# main.net
KiCad netlist of a schematic drawn in EAGLE
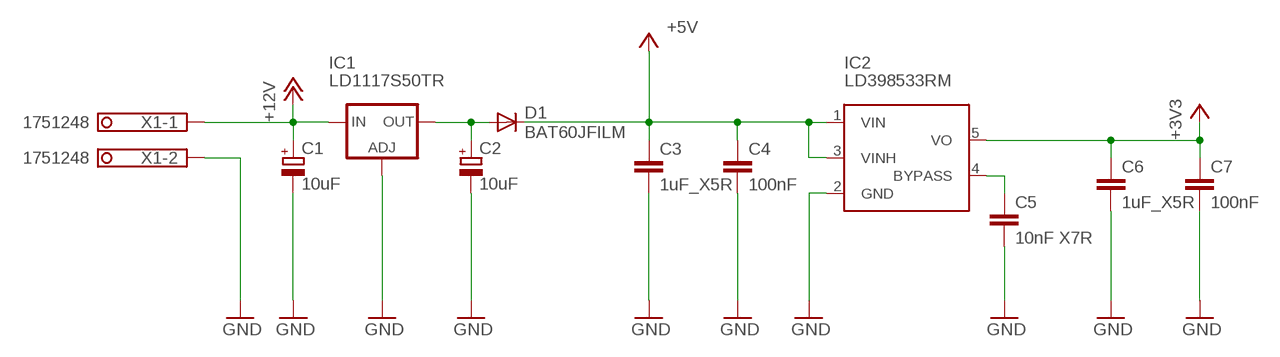
[diagram p0: schematic, sheet 1]
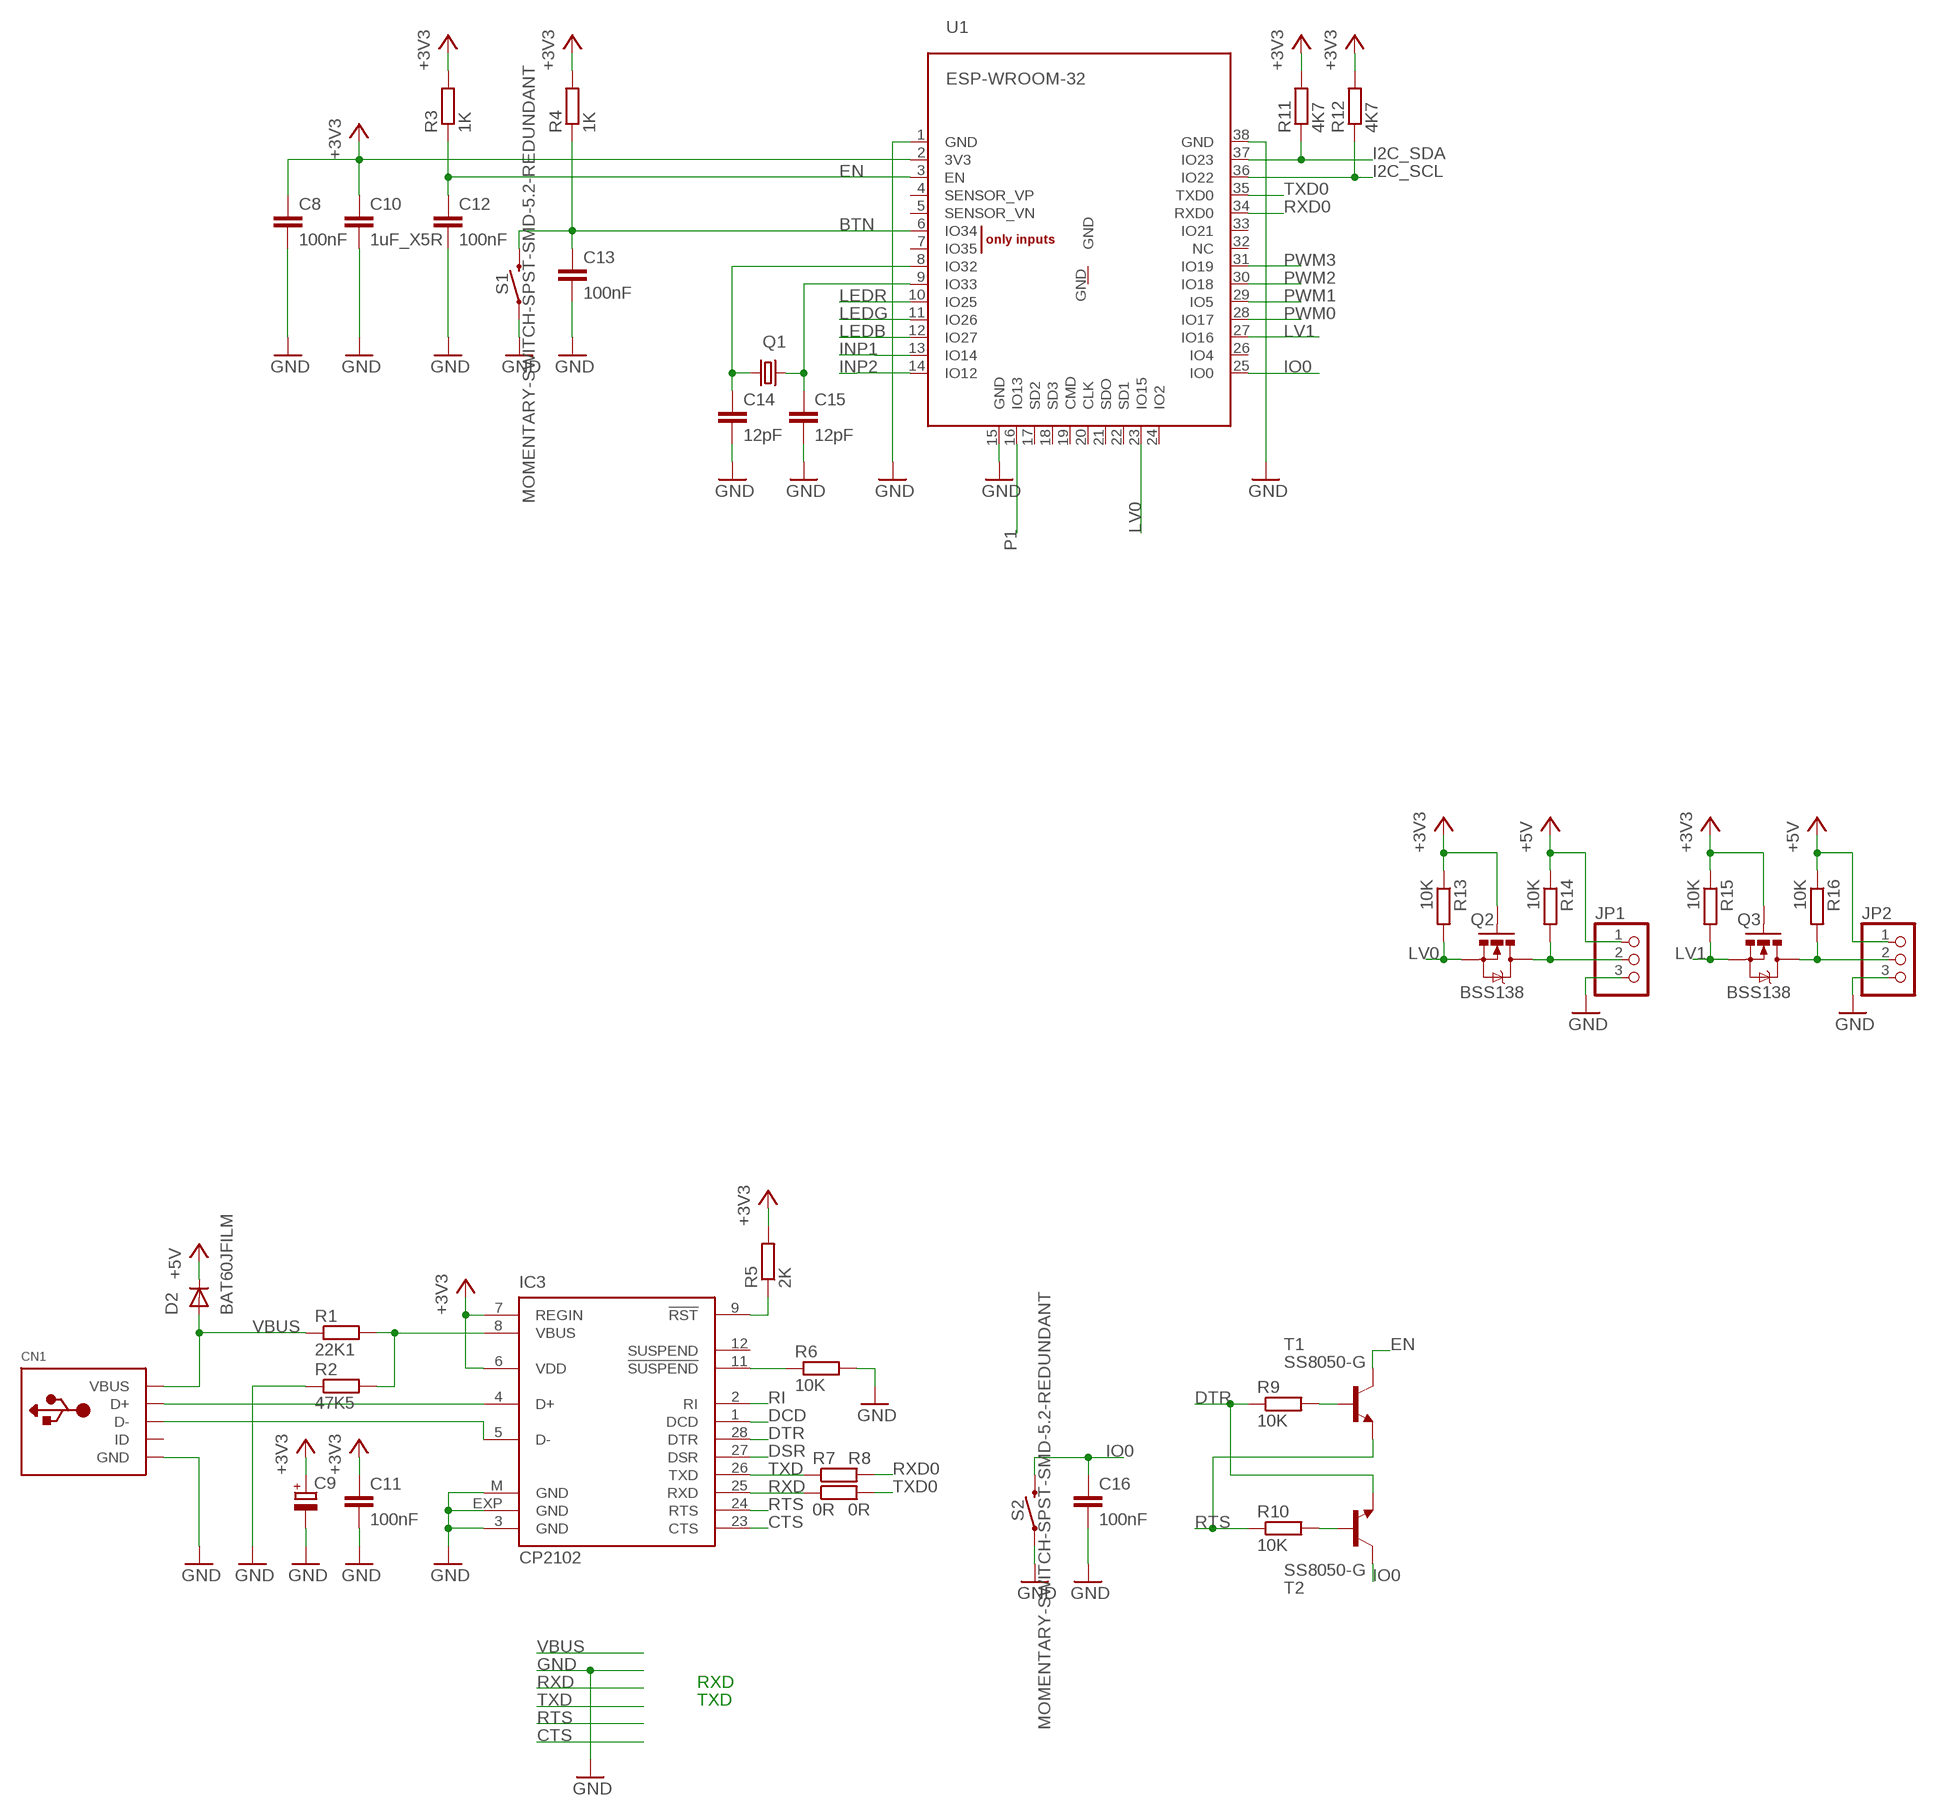
[diagram p1: schematic, sheet 2]
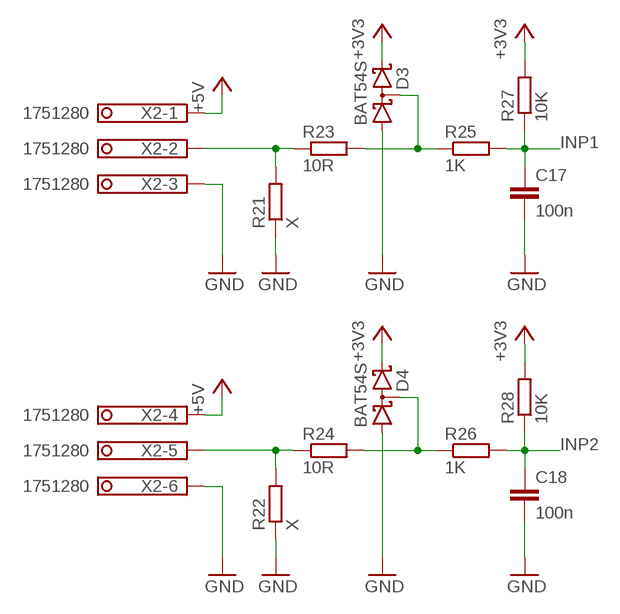
[diagram p2: schematic, sheet 3]
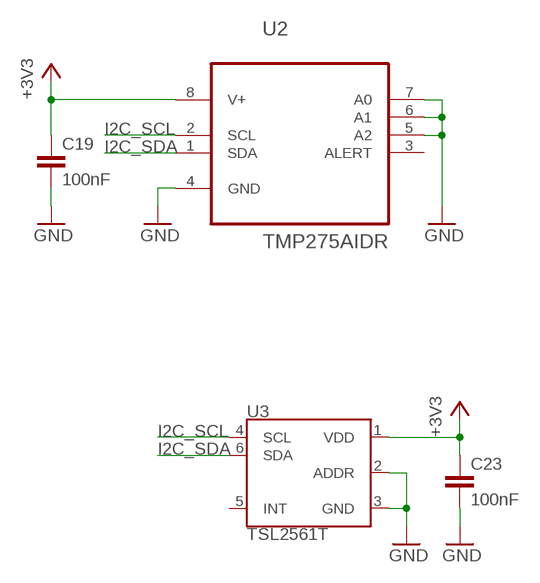
[diagram p3: schematic, sheet 4]
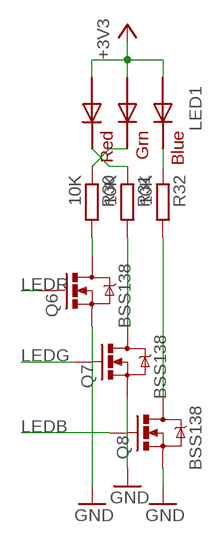
[diagram p4: schematic, sheet 5]
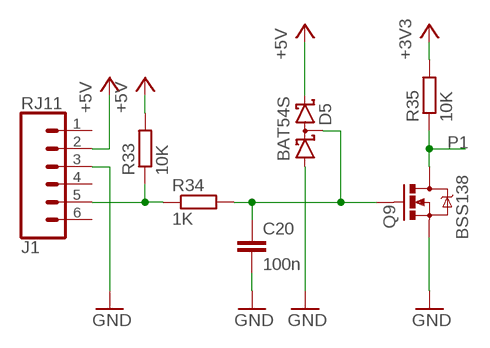
[diagram p5: schematic, sheet 6]
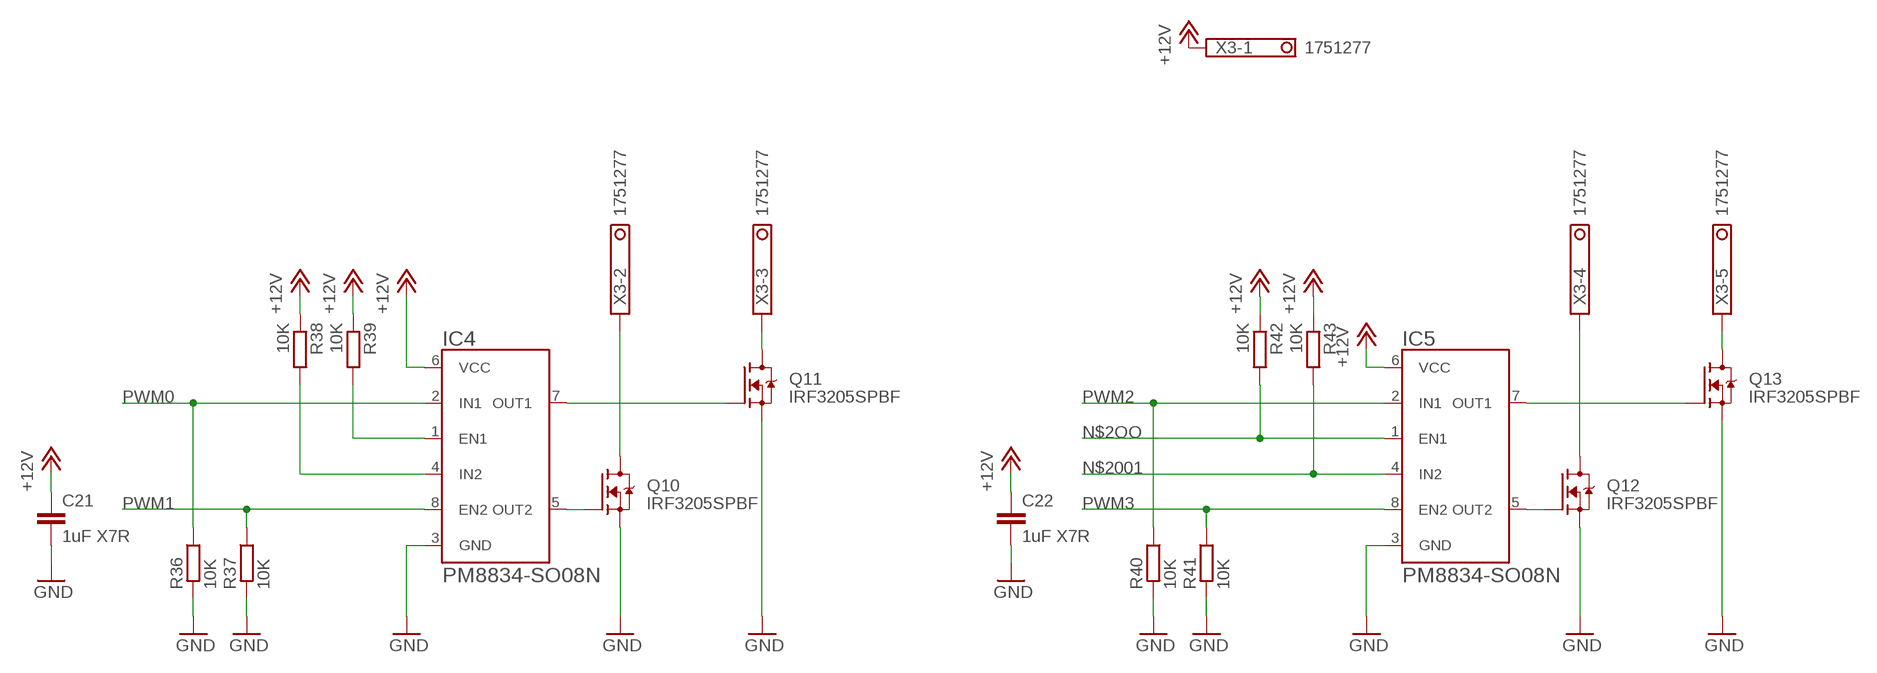
[diagram p6: schematic, sheet 7]
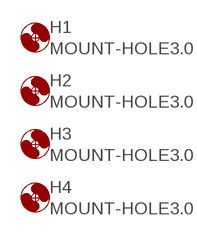
[diagram p7: schematic, sheet 8]

(export (version "E")
  (design (tool "Eeschema 10.0.6"))
  (components
    (comp (ref "C21")
      (value "1uF X7R")
      (footprint "eagle-import:C0805")
      (libsource (lib "eagle-import") (part "resistor_348_C-EUC0805"))
    )
    (comp (ref "C22")
      (value "1uF X7R")
      (footprint "eagle-import:C0805")
      (libsource (lib "eagle-import") (part "resistor_348_C-EUC0805"))
    )
    (comp (ref "IC4")
      (value "PM8834-SO08N")
      (footprint "eagle-import:SO08N")
      (fields (field (name "MF") "STMicroelectronics") (field (name "MP") "PM8834"))
      (libsource (lib "eagle-import") (part "PM8834-SO08N"))
    )
    (comp (ref "IC5")
      (value "PM8834-SO08N")
      (footprint "eagle-import:SO08N")
      (fields (field (name "MF") "STMicroelectronics") (field (name "MP") "PM8834"))
      (libsource (lib "eagle-import") (part "PM8834-SO08N"))
    )
    (comp (ref "Q10")
      (value "IRF3205SPBF")
      (footprint "eagle-import:TRANS_IRF3205SPBF")
      (fields (field (name "MF") "Infineon Technologies"))
      (libsource (lib "eagle-import") (part "IRF3205SPBF"))
    )
    (comp (ref "Q11")
      (value "IRF3205SPBF")
      (footprint "eagle-import:TRANS_IRF3205SPBF")
      (fields (field (name "MF") "Infineon Technologies"))
      (libsource (lib "eagle-import") (part "IRF3205SPBF"))
    )
    (comp (ref "Q12")
      (value "IRF3205SPBF")
      (footprint "eagle-import:TRANS_IRF3205SPBF")
      (fields (field (name "MF") "Infineon Technologies"))
      (libsource (lib "eagle-import") (part "IRF3205SPBF"))
    )
    (comp (ref "Q13")
      (value "IRF3205SPBF")
      (footprint "eagle-import:TRANS_IRF3205SPBF")
      (fields (field (name "MF") "Infineon Technologies"))
      (libsource (lib "eagle-import") (part "IRF3205SPBF"))
    )
    (comp (ref "R36")
      (value "10K")
      (footprint "eagle-import:R0805")
      (libsource (lib "eagle-import") (part "resistor_348_R-EU_R0805"))
    )
    (comp (ref "R37")
      (value "10K")
      (footprint "eagle-import:R0805")
      (libsource (lib "eagle-import") (part "resistor_348_R-EU_R0805"))
    )
    (comp (ref "R38")
      (value "10K")
      (footprint "eagle-import:R0805")
      (libsource (lib "eagle-import") (part "resistor_348_R-EU_R0805"))
    )
    (comp (ref "R39")
      (value "10K")
      (footprint "eagle-import:R0805")
      (libsource (lib "eagle-import") (part "resistor_348_R-EU_R0805"))
    )
    (comp (ref "R40")
      (value "10K")
      (footprint "eagle-import:R0805")
      (libsource (lib "eagle-import") (part "resistor_348_R-EU_R0805"))
    )
    (comp (ref "R41")
      (value "10K")
      (footprint "eagle-import:R0805")
      (libsource (lib "eagle-import") (part "resistor_348_R-EU_R0805"))
    )
    (comp (ref "R42")
      (value "10K")
      (footprint "eagle-import:R0805")
      (libsource (lib "eagle-import") (part "resistor_348_R-EU_R0805"))
    )
    (comp (ref "R43")
      (value "10K")
      (footprint "eagle-import:R0805")
      (libsource (lib "eagle-import") (part "resistor_348_R-EU_R0805"))
    )
    (comp (ref "X3")
      (value "1751277")
      (footprint "eagle-import:1751277")
      (libsource (lib "eagle-import") (part "1751277"))
    )
    (comp (ref "C20")
      (value "100n")
      (footprint "eagle-import:C0805")
      (libsource (lib "eagle-import") (part "resistor_348_C-EUC0805"))
    )
    (comp (ref "D5")
      (value "BAT54S")
      (footprint "eagle-import:SOT23")
      (libsource (lib "eagle-import") (part "BAT54S"))
    )
    (comp (ref "J1")
      (value "RJ11")
      (footprint "eagle-import:RJ11-6")
      (libsource (lib "eagle-import") (part "RJ11-6"))
    )
    (comp (ref "Q9")
      (value "BSS138")
      (footprint "eagle-import:SOT23-3")
      (libsource (lib "eagle-import") (part "MOSFET-NCHANNELSMD"))
    )
    (comp (ref "R33")
      (value "10K")
      (footprint "eagle-import:R0805")
      (libsource (lib "eagle-import") (part "resistor_348_R-EU_R0805"))
    )
    (comp (ref "R34")
      (value "1K")
      (footprint "eagle-import:R0805")
      (libsource (lib "eagle-import") (part "resistor_348_R-EU_R0805"))
    )
    (comp (ref "R35")
      (value "10K")
      (footprint "eagle-import:R0805")
      (libsource (lib "eagle-import") (part "resistor_348_R-EU_R0805"))
    )
    (comp (ref "C8")
      (value "100nF")
      (footprint "eagle-import:C0805")
      (libsource (lib "eagle-import") (part "resistor_348_C-EUC0805"))
    )
    (comp (ref "C9")
      (value "CPOL-EUSMCA")
      (footprint "eagle-import:SMC_A")
      (libsource (lib "eagle-import") (part "CPOL-EUSMCA"))
    )
    (comp (ref "C10")
      (value "1uF_X5R")
      (footprint "eagle-import:C0805")
      (libsource (lib "eagle-import") (part "resistor_348_C-EUC0805"))
    )
    (comp (ref "C11")
      (value "100nF")
      (footprint "eagle-import:C0805")
      (libsource (lib "eagle-import") (part "resistor_348_C-EUC0805"))
    )
    (comp (ref "C12")
      (value "100nF")
      (footprint "eagle-import:C0805")
      (libsource (lib "eagle-import") (part "resistor_348_C-EUC0805"))
    )
    (comp (ref "C13")
      (value "100nF")
      (footprint "eagle-import:C0805")
      (libsource (lib "eagle-import") (part "resistor_348_C-EUC0805"))
    )
    (comp (ref "C14")
      (value "12pF")
      (footprint "eagle-import:C0805")
      (libsource (lib "eagle-import") (part "resistor_348_C-EUC0805"))
    )
    (comp (ref "C15")
      (value "12pF")
      (footprint "eagle-import:C0805")
      (libsource (lib "eagle-import") (part "resistor_348_C-EUC0805"))
    )
    (comp (ref "C16")
      (value "100nF")
      (footprint "eagle-import:C0805")
      (libsource (lib "eagle-import") (part "resistor_348_C-EUC0805"))
    )
    (comp (ref "CN1")
      (value "USBMINIB")
      (footprint "eagle-import:USB-MINIB")
      (libsource (lib "eagle-import") (part "USBMINIB"))
    )
    (comp (ref "D2")
      (value "BAT60JFILM")
      (footprint "eagle-import:SOD323-W")
      (libsource (lib "eagle-import") (part "DIODE-SOD323-W"))
    )
    (comp (ref "IC3")
      (value "CP2102")
      (footprint "eagle-import:MLP28")
      (fields (field (name "MF") "FARNELL") (field (name "MPN") "CP2102-GM"))
      (libsource (lib "eagle-import") (part "CP2102"))
    )
    (comp (ref "JP1")
      (value "PINHD-1X3")
      (footprint "eagle-import:1X03")
      (libsource (lib "eagle-import") (part "PINHD-1X3"))
    )
    (comp (ref "JP2")
      (value "PINHD-1X3")
      (footprint "eagle-import:1X03")
      (libsource (lib "eagle-import") (part "PINHD-1X3"))
    )
    (comp (ref "Q1")
      (value "CRYSTALTC38H")
      (footprint "eagle-import:TC38H")
      (libsource (lib "eagle-import") (part "CRYSTALTC38H"))
    )
    (comp (ref "Q2")
      (value "BSS138")
      (footprint "eagle-import:SOT23-3")
      (libsource (lib "eagle-import") (part "MOSFET-NCHANNELSMD"))
    )
    (comp (ref "Q3")
      (value "BSS138")
      (footprint "eagle-import:SOT23-3")
      (libsource (lib "eagle-import") (part "MOSFET-NCHANNELSMD"))
    )
    (comp (ref "R1")
      (value "22K1")
      (footprint "eagle-import:R0805")
      (libsource (lib "eagle-import") (part "resistor_348_R-EU_R0805"))
    )
    (comp (ref "R2")
      (value "47K5")
      (footprint "eagle-import:R0805")
      (libsource (lib "eagle-import") (part "resistor_348_R-EU_R0805"))
    )
    (comp (ref "R3")
      (value "1K")
      (footprint "eagle-import:R0805")
      (libsource (lib "eagle-import") (part "R-EU_R0805"))
    )
    (comp (ref "R4")
      (value "1K")
      (footprint "eagle-import:R0805")
      (libsource (lib "eagle-import") (part "R-EU_R0805"))
    )
    (comp (ref "R5")
      (value "2K")
      (footprint "eagle-import:R0805")
      (libsource (lib "eagle-import") (part "resistor_348_R-EU_R0805"))
    )
    (comp (ref "R6")
      (value "10K")
      (footprint "eagle-import:R0805")
      (libsource (lib "eagle-import") (part "resistor_348_R-EU_R0805"))
    )
    (comp (ref "R7")
      (value "0R")
      (footprint "eagle-import:R0805")
      (libsource (lib "eagle-import") (part "resistor_348_R-EU_R0805"))
    )
    (comp (ref "R8")
      (value "0R")
      (footprint "eagle-import:R0805")
      (libsource (lib "eagle-import") (part "resistor_348_R-EU_R0805"))
    )
    (comp (ref "R9")
      (value "10K")
      (footprint "eagle-import:R0805")
      (libsource (lib "eagle-import") (part "R-EU_R0805"))
    )
    (comp (ref "R10")
      (value "10K")
      (footprint "eagle-import:R0805")
      (libsource (lib "eagle-import") (part "R-EU_R0805"))
    )
    (comp (ref "R11")
      (value "4K7")
      (footprint "eagle-import:R0805")
      (libsource (lib "eagle-import") (part "resistor_348_R-EU_R0805"))
    )
    (comp (ref "R12")
      (value "4K7")
      (footprint "eagle-import:R0805")
      (libsource (lib "eagle-import") (part "resistor_348_R-EU_R0805"))
    )
    (comp (ref "R13")
      (value "10K")
      (footprint "eagle-import:R0805")
      (libsource (lib "eagle-import") (part "resistor_348_R-EU_R0805"))
    )
    (comp (ref "R14")
      (value "10K")
      (footprint "eagle-import:R0805")
      (libsource (lib "eagle-import") (part "resistor_348_R-EU_R0805"))
    )
    (comp (ref "R15")
      (value "10K")
      (footprint "eagle-import:R0805")
      (libsource (lib "eagle-import") (part "resistor_348_R-EU_R0805"))
    )
    (comp (ref "R16")
      (value "10K")
      (footprint "eagle-import:R0805")
      (libsource (lib "eagle-import") (part "resistor_348_R-EU_R0805"))
    )
    (comp (ref "S1")
      (value "MOMENTARY-SWITCH-SPST-SMD-5.2-REDUNDANT")
      (footprint "eagle-import:TACTILE_SWITCH_SMD_5.2MM")
      (libsource (lib "eagle-import") (part "MOMENTARY-SWITCH-SPST-SMD-5.2-REDUNDANT"))
    )
    (comp (ref "S2")
      (value "MOMENTARY-SWITCH-SPST-SMD-5.2-REDUNDANT")
      (footprint "eagle-import:TACTILE_SWITCH_SMD_5.2MM")
      (libsource (lib "eagle-import") (part "MOMENTARY-SWITCH-SPST-SMD-5.2-REDUNDANT"))
    )
    (comp (ref "T1")
      (value "SS8050-G")
      (footprint "eagle-import:SOT23-BEC")
      (libsource (lib "eagle-import") (part "-NPN-SOT23-BECBCF29"))
    )
    (comp (ref "T2")
      (value "SS8050-G")
      (footprint "eagle-import:SOT23-BEC")
      (libsource (lib "eagle-import") (part "-NPN-SOT23-BECBCF29"))
    )
    (comp (ref "U1")
      (value "ESP-WROOM-32")
      (footprint "eagle-import:ESP-WROOM-32")
      (libsource (lib "eagle-import") (part "ESP-WROOM-32"))
    )
    (comp (ref "C19")
      (value "100nF")
      (footprint "eagle-import:C0805")
      (libsource (lib "eagle-import") (part "C-EUC0805"))
    )
    (comp (ref "C23")
      (value "100nF")
      (footprint "eagle-import:C0805")
      (libsource (lib "eagle-import") (part "C-EUC0805"))
    )
    (comp (ref "U2")
      (value "TMP275AIDR")
      (footprint "eagle-import:SOIC127P600X175-8N")
      (fields (field (name "MF") "Texas Instruments"))
      (libsource (lib "eagle-import") (part "TMP275AIDR"))
    )
    (comp (ref "U3")
      (value "TSL2561T")
      (footprint "eagle-import:TMB-6")
      (libsource (lib "eagle-import") (part "TSL2561T"))
    )
    (comp (ref "C1")
      (value "10uF")
      (footprint "eagle-import:SMC_C")
      (libsource (lib "eagle-import") (part "CPOL-EUSMCC"))
    )
    (comp (ref "C2")
      (value "10uF")
      (footprint "eagle-import:SMC_C")
      (libsource (lib "eagle-import") (part "CPOL-EUSMCC"))
    )
    (comp (ref "C3")
      (value "1uF_X5R")
      (footprint "eagle-import:C0805")
      (libsource (lib "eagle-import") (part "resistor_348_C-EUC0805"))
    )
    (comp (ref "C4")
      (value "100nF")
      (footprint "eagle-import:C0805")
      (libsource (lib "eagle-import") (part "resistor_348_C-EUC0805"))
    )
    (comp (ref "C5")
      (value "10nF X7R")
      (footprint "eagle-import:C0805")
      (libsource (lib "eagle-import") (part "resistor_348_C-EUC0805"))
    )
    (comp (ref "C6")
      (value "1uF_X5R")
      (footprint "eagle-import:C0805")
      (libsource (lib "eagle-import") (part "resistor_348_C-EUC0805"))
    )
    (comp (ref "C7")
      (value "100nF")
      (footprint "eagle-import:C0805")
      (libsource (lib "eagle-import") (part "resistor_348_C-EUC0805"))
    )
    (comp (ref "D1")
      (value "BAT60JFILM")
      (footprint "eagle-import:SOD323-W")
      (libsource (lib "eagle-import") (part "DIODE-SOD323-W"))
    )
    (comp (ref "IC1")
      (value "LD1117S50TR")
      (footprint "eagle-import:SOT223")
      (libsource (lib "eagle-import") (part "LD117A?S50TR"))
    )
    (comp (ref "IC2")
      (value "LD398533RM")
      (footprint "eagle-import:SOT23-5L")
      (libsource (lib "eagle-import") (part "LD3985M33R"))
    )
    (comp (ref "X1")
      (value "1751248")
      (footprint "eagle-import:1751248")
      (libsource (lib "eagle-import") (part "1751248"))
    )
    (comp (ref "C17")
      (value "100n")
      (footprint "eagle-import:C0805")
      (libsource (lib "eagle-import") (part "resistor_348_C-EUC0805"))
    )
    (comp (ref "C18")
      (value "100n")
      (footprint "eagle-import:C0805")
      (libsource (lib "eagle-import") (part "resistor_348_C-EUC0805"))
    )
    (comp (ref "D3")
      (value "BAT54S")
      (footprint "eagle-import:SOT23")
      (libsource (lib "eagle-import") (part "BAT54S"))
    )
    (comp (ref "D4")
      (value "BAT54S")
      (footprint "eagle-import:SOT23")
      (libsource (lib "eagle-import") (part "BAT54S"))
    )
    (comp (ref "R21")
      (value "X")
      (footprint "eagle-import:R0805")
      (libsource (lib "eagle-import") (part "resistor_348_R-EU_R0805"))
    )
    (comp (ref "R22")
      (value "X")
      (footprint "eagle-import:R0805")
      (libsource (lib "eagle-import") (part "resistor_348_R-EU_R0805"))
    )
    (comp (ref "R23")
      (value "10R")
      (footprint "eagle-import:R0805")
      (libsource (lib "eagle-import") (part "resistor_348_R-EU_R0805"))
    )
    (comp (ref "R24")
      (value "10R")
      (footprint "eagle-import:R0805")
      (libsource (lib "eagle-import") (part "resistor_348_R-EU_R0805"))
    )
    (comp (ref "R25")
      (value "1K")
      (footprint "eagle-import:R0805")
      (libsource (lib "eagle-import") (part "resistor_348_R-EU_R0805"))
    )
    (comp (ref "R26")
      (value "1K")
      (footprint "eagle-import:R0805")
      (libsource (lib "eagle-import") (part "resistor_348_R-EU_R0805"))
    )
    (comp (ref "R27")
      (value "10K")
      (footprint "eagle-import:R0805")
      (libsource (lib "eagle-import") (part "resistor_348_R-EU_R0805"))
    )
    (comp (ref "R28")
      (value "10K")
      (footprint "eagle-import:R0805")
      (libsource (lib "eagle-import") (part "resistor_348_R-EU_R0805"))
    )
    (comp (ref "X2")
      (value "1751280")
      (footprint "eagle-import:1751280")
      (libsource (lib "eagle-import") (part "1751280"))
    )
    (comp (ref "H1")
      (value "MOUNT-HOLE3.0")
      (footprint "eagle-import:3,0")
      (libsource (lib "eagle-import") (part "MOUNT-HOLE3.0"))
    )
    (comp (ref "H2")
      (value "MOUNT-HOLE3.0")
      (footprint "eagle-import:3,0")
      (libsource (lib "eagle-import") (part "MOUNT-HOLE3.0"))
    )
    (comp (ref "H3")
      (value "MOUNT-HOLE3.0")
      (footprint "eagle-import:3,0")
      (libsource (lib "eagle-import") (part "MOUNT-HOLE3.0"))
    )
    (comp (ref "H4")
      (value "MOUNT-HOLE3.0")
      (footprint "eagle-import:3,0")
      (libsource (lib "eagle-import") (part "MOUNT-HOLE3.0"))
    )
    (comp (ref "LED1")
      (value "RGBLED5050")
      (footprint "eagle-import:RGBLED5050")
      (libsource (lib "eagle-import") (part "RGBLED5050"))
    )
    (comp (ref "Q6")
      (value "BSS138")
      (footprint "eagle-import:SOT23-3")
      (libsource (lib "eagle-import") (part "MOSFET-NCHANNELSMD"))
    )
    (comp (ref "Q7")
      (value "BSS138")
      (footprint "eagle-import:SOT23-3")
      (libsource (lib "eagle-import") (part "MOSFET-NCHANNELSMD"))
    )
    (comp (ref "Q8")
      (value "BSS138")
      (footprint "eagle-import:SOT23-3")
      (libsource (lib "eagle-import") (part "MOSFET-NCHANNELSMD"))
    )
    (comp (ref "R30")
      (value "10K")
      (footprint "eagle-import:R0805")
      (libsource (lib "eagle-import") (part "resistor_348_R-EU_R0805"))
    )
    (comp (ref "R31")
      (value "10K")
      (footprint "eagle-import:R0805")
      (libsource (lib "eagle-import") (part "resistor_348_R-EU_R0805"))
    )
    (comp (ref "R32")
      (value "10K")
      (footprint "eagle-import:R0805")
      (libsource (lib "eagle-import") (part "resistor_348_R-EU_R0805"))
    )
  )
  (nets
    (net (code "1") (name "+3V3") (class "Default")
      (node (ref "C10") (pin "1") (pinfunction "1_1") (pintype "passive"))
      (node (ref "C11") (pin "1") (pinfunction "1_1") (pintype "passive"))
      (node (ref "C19") (pin "1") (pinfunction "1_1") (pintype "passive"))
      (node (ref "C23") (pin "1") (pinfunction "1_1") (pintype "passive"))
      (node (ref "C6") (pin "1") (pinfunction "1_1") (pintype "passive"))
      (node (ref "C7") (pin "1") (pinfunction "1_1") (pintype "passive"))
      (node (ref "C8") (pin "1") (pinfunction "1_1") (pintype "passive"))
      (node (ref "C9") (pin "+") (pinfunction "+_+") (pintype "passive"))
      (node (ref "D3") (pin "2") (pinfunction "C2_2") (pintype "passive"))
      (node (ref "D4") (pin "2") (pinfunction "C2_2") (pintype "passive"))
      (node (ref "IC2") (pin "5") (pinfunction "VO_5") (pintype "output"))
      (node (ref "IC3") (pin "6") (pinfunction "VDD_6") (pintype "power_in"))
      (node (ref "IC3") (pin "7") (pinfunction "REGIN_7") (pintype "passive"))
      (node (ref "LED1") (pin "1") (pinfunction "GREEN_A_1") (pintype "bidirectional"))
      (node (ref "LED1") (pin "2") (pinfunction "RED_A_2") (pintype "bidirectional"))
      (node (ref "LED1") (pin "3") (pinfunction "BLUE_A_3") (pintype "bidirectional"))
      (node (ref "Q2") (pin "1") (pinfunction "G_1") (pintype "passive"))
      (node (ref "Q3") (pin "1") (pinfunction "G_1") (pintype "passive"))
      (node (ref "R11") (pin "2") (pinfunction "2_2") (pintype "passive"))
      (node (ref "R12") (pin "2") (pinfunction "2_2") (pintype "passive"))
      (node (ref "R13") (pin "1") (pinfunction "1_1") (pintype "passive"))
      (node (ref "R15") (pin "1") (pinfunction "1_1") (pintype "passive"))
      (node (ref "R27") (pin "2") (pinfunction "2_2") (pintype "passive"))
      (node (ref "R28") (pin "2") (pinfunction "2_2") (pintype "passive"))
      (node (ref "R3") (pin "2") (pinfunction "2_2") (pintype "passive"))
      (node (ref "R35") (pin "2") (pinfunction "2_2") (pintype "passive"))
      (node (ref "R4") (pin "2") (pinfunction "2_2") (pintype "passive"))
      (node (ref "R5") (pin "2") (pinfunction "2_2") (pintype "passive"))
      (node (ref "U1") (pin "2") (pinfunction "3V3_2") (pintype "bidirectional"))
      (node (ref "U2") (pin "8") (pinfunction "V+_8") (pintype "power_in"))
      (node (ref "U3") (pin "1") (pinfunction "VDD_1") (pintype "power_in"))
    )
    (net (code "2") (name "+5V") (class "Default")
      (node (ref "C3") (pin "1") (pinfunction "1_1") (pintype "passive"))
      (node (ref "C4") (pin "1") (pinfunction "1_1") (pintype "passive"))
      (node (ref "D1") (pin "C") (pinfunction "C_C") (pintype "passive"))
      (node (ref "D2") (pin "C") (pinfunction "C_C") (pintype "passive"))
      (node (ref "D5") (pin "2") (pinfunction "C2_2") (pintype "passive"))
      (node (ref "IC2") (pin "1") (pinfunction "VIN_1") (pintype "input"))
      (node (ref "IC2") (pin "3") (pinfunction "VINH_3") (pintype "input"))
      (node (ref "J1") (pin "2") (pinfunction "2_2") (pintype "passive"))
      (node (ref "JP1") (pin "1") (pinfunction "1_1") (pintype "passive"))
      (node (ref "JP2") (pin "1") (pinfunction "1_1") (pintype "passive"))
      (node (ref "R14") (pin "1") (pinfunction "1_1") (pintype "passive"))
      (node (ref "R16") (pin "1") (pinfunction "1_1") (pintype "passive"))
      (node (ref "R33") (pin "2") (pinfunction "2_2") (pintype "passive"))
      (node (ref "X2") (pin "1") (pinfunction "K_1") (pintype "passive"))
      (node (ref "X2") (pin "4") (pinfunction "K_4") (pintype "passive"))
    )
    (net (code "3") (name "+12V") (class "Default")
      (node (ref "C1") (pin "+") (pinfunction "+_+") (pintype "passive"))
      (node (ref "C21") (pin "1") (pinfunction "1_1") (pintype "passive"))
      (node (ref "C22") (pin "1") (pinfunction "1_1") (pintype "passive"))
      (node (ref "IC1") (pin "3") (pinfunction "IN_3") (pintype "input"))
      (node (ref "IC4") (pin "6") (pinfunction "VCC_6") (pintype "power_in"))
      (node (ref "IC5") (pin "6") (pinfunction "VCC_6") (pintype "power_in"))
      (node (ref "R38") (pin "2") (pinfunction "2_2") (pintype "passive"))
      (node (ref "R39") (pin "2") (pinfunction "2_2") (pintype "passive"))
      (node (ref "R42") (pin "2") (pinfunction "2_2") (pintype "passive"))
      (node (ref "R43") (pin "2") (pinfunction "2_2") (pintype "passive"))
      (node (ref "X1") (pin "1") (pinfunction "K_1") (pintype "passive"))
      (node (ref "X3") (pin "1") (pinfunction "K_1") (pintype "passive"))
    )
    (net (code "4") (name "BTN") (class "Default")
      (node (ref "C13") (pin "1") (pinfunction "1_1") (pintype "passive"))
      (node (ref "R4") (pin "1") (pinfunction "1_1") (pintype "passive"))
      (node (ref "S1") (pin "3") (pinfunction "2_3") (pintype "passive"))
      (node (ref "S1") (pin "4") (pinfunction "2_4") (pintype "passive"))
      (node (ref "U1") (pin "6") (pinfunction "IO34_6") (pintype "input"))
    )
    (net (code "5") (name "CTS") (class "Default")
      (node (ref "IC3") (pin "23") (pinfunction "CTS_23") (pintype "input"))
    )
    (net (code "6") (name "DCD") (class "Default")
      (node (ref "IC3") (pin "1") (pinfunction "DCD_1") (pintype "input"))
    )
    (net (code "7") (name "DSR") (class "Default")
      (node (ref "IC3") (pin "27") (pinfunction "DSR_27") (pintype "input"))
    )
    (net (code "8") (name "DTR") (class "Default")
      (node (ref "IC3") (pin "28") (pinfunction "DTR_28") (pintype "output"))
      (node (ref "R9") (pin "1") (pinfunction "1_1") (pintype "passive"))
      (node (ref "T2") (pin "E") (pinfunction "E_E") (pintype "passive"))
    )
    (net (code "9") (name "EN") (class "Default")
      (node (ref "C12") (pin "1") (pinfunction "1_1") (pintype "passive"))
      (node (ref "R3") (pin "1") (pinfunction "1_1") (pintype "passive"))
      (node (ref "T1") (pin "C") (pinfunction "C_C") (pintype "passive"))
      (node (ref "U1") (pin "3") (pinfunction "EN_3") (pintype "bidirectional"))
    )
    (net (code "10") (name "GND") (class "Default")
      (node (ref "C1") (pin "-") (pinfunction "-_-") (pintype "passive"))
      (node (ref "C10") (pin "2") (pinfunction "2_2") (pintype "passive"))
      (node (ref "C11") (pin "2") (pinfunction "2_2") (pintype "passive"))
      (node (ref "C12") (pin "2") (pinfunction "2_2") (pintype "passive"))
      (node (ref "C13") (pin "2") (pinfunction "2_2") (pintype "passive"))
      (node (ref "C14") (pin "2") (pinfunction "2_2") (pintype "passive"))
      (node (ref "C15") (pin "2") (pinfunction "2_2") (pintype "passive"))
      (node (ref "C16") (pin "2") (pinfunction "2_2") (pintype "passive"))
      (node (ref "C17") (pin "2") (pinfunction "2_2") (pintype "passive"))
      (node (ref "C18") (pin "2") (pinfunction "2_2") (pintype "passive"))
      (node (ref "C19") (pin "2") (pinfunction "2_2") (pintype "passive"))
      (node (ref "C2") (pin "-") (pinfunction "-_-") (pintype "passive"))
      (node (ref "C20") (pin "2") (pinfunction "2_2") (pintype "passive"))
      (node (ref "C21") (pin "2") (pinfunction "2_2") (pintype "passive"))
      (node (ref "C22") (pin "2") (pinfunction "2_2") (pintype "passive"))
      (node (ref "C23") (pin "2") (pinfunction "2_2") (pintype "passive"))
      (node (ref "C3") (pin "2") (pinfunction "2_2") (pintype "passive"))
      (node (ref "C4") (pin "2") (pinfunction "2_2") (pintype "passive"))
      (node (ref "C5") (pin "2") (pinfunction "2_2") (pintype "passive"))
      (node (ref "C6") (pin "2") (pinfunction "2_2") (pintype "passive"))
      (node (ref "C7") (pin "2") (pinfunction "2_2") (pintype "passive"))
      (node (ref "C8") (pin "2") (pinfunction "2_2") (pintype "passive"))
      (node (ref "C9") (pin "-") (pinfunction "-_-") (pintype "passive"))
      (node (ref "CN1") (pin "GND") (pinfunction "GND_GND") (pintype "power_in"))
      (node (ref "D3") (pin "1") (pinfunction "A1_1") (pintype "passive"))
      (node (ref "D4") (pin "1") (pinfunction "A1_1") (pintype "passive"))
      (node (ref "D5") (pin "1") (pinfunction "A1_1") (pintype "passive"))
      (node (ref "IC1") (pin "1") (pinfunction "ADJ_1") (pintype "input"))
      (node (ref "IC2") (pin "2") (pinfunction "GND_2") (pintype "power_in"))
      (node (ref "IC3") (pin "3") (pinfunction "GND_3") (pintype "power_in"))
      (node (ref "IC3") (pin "EXP") (pinfunction "GND_EXP") (pintype "power_in"))
      (node (ref "IC3") (pin "M") (pinfunction "GND_M") (pintype "power_in"))
      (node (ref "IC4") (pin "3") (pinfunction "GND_3") (pintype "power_in"))
      (node (ref "IC5") (pin "3") (pinfunction "GND_3") (pintype "power_in"))
      (node (ref "J1") (pin "3") (pinfunction "3_3") (pintype "passive"))
      (node (ref "JP1") (pin "3") (pinfunction "3_3") (pintype "passive"))
      (node (ref "JP2") (pin "3") (pinfunction "3_3") (pintype "passive"))
      (node (ref "Q10") (pin "3") (pinfunction "S_3") (pintype "passive"))
      (node (ref "Q11") (pin "3") (pinfunction "S_3") (pintype "passive"))
      (node (ref "Q12") (pin "3") (pinfunction "S_3") (pintype "passive"))
      (node (ref "Q13") (pin "3") (pinfunction "S_3") (pintype "passive"))
      (node (ref "Q6") (pin "2") (pinfunction "S_2") (pintype "passive"))
      (node (ref "Q7") (pin "2") (pinfunction "S_2") (pintype "passive"))
      (node (ref "Q8") (pin "2") (pinfunction "S_2") (pintype "passive"))
      (node (ref "Q9") (pin "2") (pinfunction "S_2") (pintype "passive"))
      (node (ref "R2") (pin "1") (pinfunction "1_1") (pintype "passive"))
      (node (ref "R21") (pin "1") (pinfunction "1_1") (pintype "passive"))
      (node (ref "R22") (pin "1") (pinfunction "1_1") (pintype "passive"))
      (node (ref "R36") (pin "2") (pinfunction "2_2") (pintype "passive"))
      (node (ref "R37") (pin "2") (pinfunction "2_2") (pintype "passive"))
      (node (ref "R40") (pin "2") (pinfunction "2_2") (pintype "passive"))
      (node (ref "R41") (pin "2") (pinfunction "2_2") (pintype "passive"))
      (node (ref "R6") (pin "2") (pinfunction "2_2") (pintype "passive"))
      (node (ref "S1") (pin "1") (pinfunction "1_1") (pintype "passive"))
      (node (ref "S1") (pin "2") (pinfunction "1_2") (pintype "passive"))
      (node (ref "S2") (pin "1") (pinfunction "1_1") (pintype "passive"))
      (node (ref "S2") (pin "2") (pinfunction "1_2") (pintype "passive"))
      (node (ref "U1") (pin "1") (pinfunction "GND_1") (pintype "bidirectional"))
      (node (ref "U1") (pin "15") (pinfunction "GND_15") (pintype "bidirectional"))
      (node (ref "U1") (pin "38") (pinfunction "GND_38") (pintype "bidirectional"))
      (node (ref "U2") (pin "4") (pinfunction "GND_4") (pintype "passive"))
      (node (ref "U2") (pin "5") (pinfunction "A2_5") (pintype "output"))
      (node (ref "U2") (pin "6") (pinfunction "A1_6") (pintype "output"))
      (node (ref "U2") (pin "7") (pinfunction "A0_7") (pintype "output"))
      (node (ref "U3") (pin "2") (pinfunction "ADDR_2") (pintype "input"))
      (node (ref "U3") (pin "3") (pinfunction "GND_3") (pintype "power_in"))
      (node (ref "X1") (pin "2") (pinfunction "K_2") (pintype "passive"))
      (node (ref "X2") (pin "3") (pinfunction "K_3") (pintype "passive"))
      (node (ref "X2") (pin "6") (pinfunction "K_6") (pintype "passive"))
    )
    (net (code "11") (name "I2C_SCL") (class "Default")
      (node (ref "R12") (pin "1") (pinfunction "1_1") (pintype "passive"))
      (node (ref "U1") (pin "36") (pinfunction "IO22_36") (pintype "bidirectional"))
      (node (ref "U2") (pin "2") (pinfunction "SCL_2") (pintype "input"))
      (node (ref "U3") (pin "4") (pinfunction "SCL_4") (pintype "input"))
    )
    (net (code "12") (name "I2C_SDA") (class "Default")
      (node (ref "R11") (pin "1") (pinfunction "1_1") (pintype "passive"))
      (node (ref "U1") (pin "37") (pinfunction "IO23_37") (pintype "bidirectional"))
      (node (ref "U2") (pin "1") (pinfunction "SDA_1") (pintype "input"))
      (node (ref "U3") (pin "6") (pinfunction "SDA_6") (pintype "bidirectional"))
    )
    (net (code "13") (name "INP1") (class "Default")
      (node (ref "C17") (pin "1") (pinfunction "1_1") (pintype "passive"))
      (node (ref "R25") (pin "2") (pinfunction "2_2") (pintype "passive"))
      (node (ref "R27") (pin "1") (pinfunction "1_1") (pintype "passive"))
      (node (ref "U1") (pin "13") (pinfunction "IO14_13") (pintype "bidirectional"))
    )
    (net (code "14") (name "INP2") (class "Default")
      (node (ref "C18") (pin "1") (pinfunction "1_1") (pintype "passive"))
      (node (ref "R26") (pin "2") (pinfunction "2_2") (pintype "passive"))
      (node (ref "R28") (pin "1") (pinfunction "1_1") (pintype "passive"))
      (node (ref "U1") (pin "14") (pinfunction "IO12_14") (pintype "bidirectional"))
    )
    (net (code "15") (name "IO0") (class "Default")
      (node (ref "C16") (pin "1") (pinfunction "1_1") (pintype "passive"))
      (node (ref "S2") (pin "3") (pinfunction "2_3") (pintype "passive"))
      (node (ref "S2") (pin "4") (pinfunction "2_4") (pintype "passive"))
      (node (ref "T2") (pin "C") (pinfunction "C_C") (pintype "passive"))
      (node (ref "U1") (pin "25") (pinfunction "IO0_25") (pintype "bidirectional"))
    )
    (net (code "16") (name "LEDB") (class "Default")
      (node (ref "Q8") (pin "1") (pinfunction "G_1") (pintype "passive"))
      (node (ref "U1") (pin "12") (pinfunction "IO27_12") (pintype "bidirectional"))
    )
    (net (code "17") (name "LEDG") (class "Default")
      (node (ref "Q7") (pin "1") (pinfunction "G_1") (pintype "passive"))
      (node (ref "U1") (pin "11") (pinfunction "IO26_11") (pintype "bidirectional"))
    )
    (net (code "18") (name "LEDR") (class "Default")
      (node (ref "Q6") (pin "1") (pinfunction "G_1") (pintype "passive"))
      (node (ref "U1") (pin "10") (pinfunction "IO25_10") (pintype "bidirectional"))
    )
    (net (code "19") (name "LV0") (class "Default")
      (node (ref "Q2") (pin "2") (pinfunction "S_2") (pintype "passive"))
      (node (ref "R13") (pin "2") (pinfunction "2_2") (pintype "passive"))
      (node (ref "U1") (pin "23") (pinfunction "IO15_23") (pintype "bidirectional"))
    )
    (net (code "20") (name "LV1") (class "Default")
      (node (ref "Q3") (pin "2") (pinfunction "S_2") (pintype "passive"))
      (node (ref "R15") (pin "2") (pinfunction "2_2") (pintype "passive"))
      (node (ref "U1") (pin "27") (pinfunction "IO16_27") (pintype "bidirectional"))
    )
    (net (code "21") (name "N$2OO") (class "Default")
      (node (ref "IC5") (pin "1") (pinfunction "EN1_1") (pintype "input"))
      (node (ref "R42") (pin "1") (pinfunction "1_1") (pintype "passive"))
    )
    (net (code "22") (name "N$2001") (class "Default")
      (node (ref "IC5") (pin "4") (pinfunction "IN2_4") (pintype "input"))
      (node (ref "R43") (pin "1") (pinfunction "1_1") (pintype "passive"))
    )
    (net (code "23") (name "Net-(D3-C1A2)") (class "Default")
      (node (ref "D3") (pin "3") (pinfunction "C1A2_3") (pintype "passive"))
      (node (ref "R23") (pin "2") (pinfunction "2_2") (pintype "passive"))
      (node (ref "R25") (pin "1") (pinfunction "1_1") (pintype "passive"))
    )
    (net (code "24") (name "Net-(D4-C1A2)") (class "Default")
      (node (ref "D4") (pin "3") (pinfunction "C1A2_3") (pintype "passive"))
      (node (ref "R24") (pin "2") (pinfunction "2_2") (pintype "passive"))
      (node (ref "R26") (pin "1") (pinfunction "1_1") (pintype "passive"))
    )
    (net (code "25") (name "Net-(D5-C1A2)") (class "Default")
      (node (ref "C20") (pin "1") (pinfunction "1_1") (pintype "passive"))
      (node (ref "D5") (pin "3") (pinfunction "C1A2_3") (pintype "passive"))
      (node (ref "Q9") (pin "1") (pinfunction "G_1") (pintype "passive"))
      (node (ref "R34") (pin "2") (pinfunction "2_2") (pintype "passive"))
    )
    (net (code "26") (name "Net-(IC1-OUT)") (class "Default")
      (node (ref "C2") (pin "+") (pinfunction "+_+") (pintype "passive"))
      (node (ref "D1") (pin "A") (pinfunction "A_A") (pintype "passive"))
      (node (ref "IC1") (pin "4") (pinfunction "OUT_4") (pintype "passive"))
    )
    (net (code "27") (name "Net-(IC2-BYPASS)") (class "Default")
      (node (ref "C5") (pin "1") (pinfunction "1_1") (pintype "passive"))
      (node (ref "IC2") (pin "4") (pinfunction "BYPASS_4") (pintype "passive"))
    )
    (net (code "28") (name "Net-(IC3-D+)") (class "Default")
      (node (ref "CN1") (pin "D+") (pinfunction "D+_D+") (pintype "bidirectional"))
      (node (ref "IC3") (pin "4") (pinfunction "D+_4") (pintype "bidirectional"))
    )
    (net (code "29") (name "Net-(IC3-D-)") (class "Default")
      (node (ref "CN1") (pin "D-") (pinfunction "D-_D-") (pintype "bidirectional"))
      (node (ref "IC3") (pin "5") (pinfunction "D-_5") (pintype "bidirectional"))
    )
    (net (code "30") (name "Net-(IC3-VBUS)") (class "Default")
      (node (ref "IC3") (pin "8") (pinfunction "VBUS_8") (pintype "input"))
      (node (ref "R1") (pin "2") (pinfunction "2_2") (pintype "passive"))
      (node (ref "R2") (pin "2") (pinfunction "2_2") (pintype "passive"))
    )
    (net (code "31") (name "Net-(IC3-~{RST})") (class "Default")
      (node (ref "IC3") (pin "9") (pinfunction "~{RST}_9") (pintype "bidirectional"))
      (node (ref "R5") (pin "1") (pinfunction "1_1") (pintype "passive"))
    )
    (net (code "32") (name "Net-(IC3-~{SUSPEND})") (class "Default")
      (node (ref "IC3") (pin "11") (pinfunction "~{SUSPEND}_11") (pintype "output"))
      (node (ref "R6") (pin "1") (pinfunction "1_1") (pintype "passive"))
    )
    (net (code "33") (name "Net-(IC4-EN1)") (class "Default")
      (node (ref "IC4") (pin "1") (pinfunction "EN1_1") (pintype "input"))
      (node (ref "R39") (pin "1") (pinfunction "1_1") (pintype "passive"))
    )
    (net (code "34") (name "Net-(IC4-IN2)") (class "Default")
      (node (ref "IC4") (pin "4") (pinfunction "IN2_4") (pintype "input"))
      (node (ref "R38") (pin "1") (pinfunction "1_1") (pintype "passive"))
    )
    (net (code "35") (name "Net-(IC4-OUT1)") (class "Default")
      (node (ref "IC4") (pin "7") (pinfunction "OUT1_7") (pintype "bidirectional"))
      (node (ref "Q11") (pin "1") (pinfunction "G_1") (pintype "passive"))
    )
    (net (code "36") (name "Net-(IC4-OUT2)") (class "Default")
      (node (ref "IC4") (pin "5") (pinfunction "OUT2_5") (pintype "bidirectional"))
      (node (ref "Q10") (pin "1") (pinfunction "G_1") (pintype "passive"))
    )
    (net (code "37") (name "Net-(IC5-OUT1)") (class "Default")
      (node (ref "IC5") (pin "7") (pinfunction "OUT1_7") (pintype "bidirectional"))
      (node (ref "Q13") (pin "1") (pinfunction "G_1") (pintype "passive"))
    )
    (net (code "38") (name "Net-(IC5-OUT2)") (class "Default")
      (node (ref "IC5") (pin "5") (pinfunction "OUT2_5") (pintype "bidirectional"))
      (node (ref "Q12") (pin "1") (pinfunction "G_1") (pintype "passive"))
    )
    (net (code "39") (name "Net-(J1-Pad5)") (class "Default")
      (node (ref "J1") (pin "5") (pinfunction "5_5") (pintype "passive"))
      (node (ref "R33") (pin "1") (pinfunction "1_1") (pintype "passive"))
      (node (ref "R34") (pin "1") (pinfunction "1_1") (pintype "passive"))
    )
    (net (code "40") (name "Net-(LED1-BLUE_C)") (class "Default")
      (node (ref "LED1") (pin "4") (pinfunction "BLUE_C_4") (pintype "bidirectional"))
      (node (ref "R32") (pin "1") (pinfunction "1_1") (pintype "passive"))
    )
    (net (code "41") (name "Net-(LED1-GREEN_C)") (class "Default")
      (node (ref "LED1") (pin "6") (pinfunction "GREEN_C_6") (pintype "bidirectional"))
      (node (ref "R30") (pin "1") (pinfunction "1_1") (pintype "passive"))
    )
    (net (code "42") (name "Net-(LED1-RED_C)") (class "Default")
      (node (ref "LED1") (pin "5") (pinfunction "RED_C_5") (pintype "bidirectional"))
      (node (ref "R31") (pin "1") (pinfunction "1_1") (pintype "passive"))
    )
    (net (code "43") (name "Net-(Q2-D)") (class "Default")
      (node (ref "JP1") (pin "2") (pinfunction "2_2") (pintype "passive"))
      (node (ref "Q2") (pin "3") (pinfunction "D_3") (pintype "passive"))
      (node (ref "R14") (pin "2") (pinfunction "2_2") (pintype "passive"))
    )
    (net (code "44") (name "Net-(Q3-D)") (class "Default")
      (node (ref "JP2") (pin "2") (pinfunction "2_2") (pintype "passive"))
      (node (ref "Q3") (pin "3") (pinfunction "D_3") (pintype "passive"))
      (node (ref "R16") (pin "2") (pinfunction "2_2") (pintype "passive"))
    )
    (net (code "45") (name "Net-(Q6-D)") (class "Default")
      (node (ref "Q6") (pin "3") (pinfunction "D_3") (pintype "passive"))
      (node (ref "R30") (pin "2") (pinfunction "2_2") (pintype "passive"))
    )
    (net (code "46") (name "Net-(Q7-D)") (class "Default")
      (node (ref "Q7") (pin "3") (pinfunction "D_3") (pintype "passive"))
      (node (ref "R31") (pin "2") (pinfunction "2_2") (pintype "passive"))
    )
    (net (code "47") (name "Net-(Q8-D)") (class "Default")
      (node (ref "Q8") (pin "3") (pinfunction "D_3") (pintype "passive"))
      (node (ref "R32") (pin "2") (pinfunction "2_2") (pintype "passive"))
    )
    (net (code "48") (name "Net-(Q10-D)") (class "Default")
      (node (ref "Q10") (pin "2") (pinfunction "D_2") (pintype "passive"))
      (node (ref "X3") (pin "2") (pinfunction "K_2") (pintype "passive"))
    )
    (net (code "49") (name "Net-(Q11-D)") (class "Default")
      (node (ref "Q11") (pin "2") (pinfunction "D_2") (pintype "passive"))
      (node (ref "X3") (pin "3") (pinfunction "K_3") (pintype "passive"))
    )
    (net (code "50") (name "Net-(Q12-D)") (class "Default")
      (node (ref "Q12") (pin "2") (pinfunction "D_2") (pintype "passive"))
      (node (ref "X3") (pin "4") (pinfunction "K_4") (pintype "passive"))
    )
    (net (code "51") (name "Net-(Q13-D)") (class "Default")
      (node (ref "Q13") (pin "2") (pinfunction "D_2") (pintype "passive"))
      (node (ref "X3") (pin "5") (pinfunction "K_5") (pintype "passive"))
    )
    (net (code "52") (name "Net-(R9-Pad2)") (class "Default")
      (node (ref "R9") (pin "2") (pinfunction "2_2") (pintype "passive"))
      (node (ref "T1") (pin "B") (pinfunction "B_B") (pintype "passive"))
    )
    (net (code "53") (name "Net-(R10-Pad2)") (class "Default")
      (node (ref "R10") (pin "2") (pinfunction "2_2") (pintype "passive"))
      (node (ref "T2") (pin "B") (pinfunction "B_B") (pintype "passive"))
    )
    (net (code "54") (name "Net-(U1-IO32)") (class "Default")
      (node (ref "C14") (pin "1") (pinfunction "1_1") (pintype "passive"))
      (node (ref "Q1") (pin "2") (pinfunction "2_2") (pintype "passive"))
      (node (ref "U1") (pin "8") (pinfunction "IO32_8") (pintype "bidirectional"))
    )
    (net (code "55") (name "Net-(U1-IO33)") (class "Default")
      (node (ref "C15") (pin "1") (pinfunction "1_1") (pintype "passive"))
      (node (ref "Q1") (pin "1") (pinfunction "1_1") (pintype "passive"))
      (node (ref "U1") (pin "9") (pinfunction "IO33_9") (pintype "bidirectional"))
    )
    (net (code "56") (name "Net-(X2B-K)") (class "Default")
      (node (ref "R21") (pin "2") (pinfunction "2_2") (pintype "passive"))
      (node (ref "R23") (pin "1") (pinfunction "1_1") (pintype "passive"))
      (node (ref "X2") (pin "2") (pinfunction "K_2") (pintype "passive"))
    )
    (net (code "57") (name "Net-(X2E-K)") (class "Default")
      (node (ref "R22") (pin "2") (pinfunction "2_2") (pintype "passive"))
      (node (ref "R24") (pin "1") (pinfunction "1_1") (pintype "passive"))
      (node (ref "X2") (pin "5") (pinfunction "K_5") (pintype "passive"))
    )
    (net (code "58") (name "P1") (class "Default")
      (node (ref "Q9") (pin "3") (pinfunction "D_3") (pintype "passive"))
      (node (ref "R35") (pin "1") (pinfunction "1_1") (pintype "passive"))
      (node (ref "U1") (pin "16") (pinfunction "IO13_16") (pintype "bidirectional"))
    )
    (net (code "59") (name "PWM0") (class "Default")
      (node (ref "IC4") (pin "2") (pinfunction "IN1_2") (pintype "input"))
      (node (ref "R36") (pin "1") (pinfunction "1_1") (pintype "passive"))
      (node (ref "U1") (pin "28") (pinfunction "IO17_28") (pintype "bidirectional"))
    )
    (net (code "60") (name "PWM1") (class "Default")
      (node (ref "IC4") (pin "8") (pinfunction "EN2_8") (pintype "input"))
      (node (ref "R37") (pin "1") (pinfunction "1_1") (pintype "passive"))
      (node (ref "U1") (pin "29") (pinfunction "IO5_29") (pintype "bidirectional"))
    )
    (net (code "61") (name "PWM2") (class "Default")
      (node (ref "IC5") (pin "2") (pinfunction "IN1_2") (pintype "input"))
      (node (ref "R40") (pin "1") (pinfunction "1_1") (pintype "passive"))
      (node (ref "U1") (pin "30") (pinfunction "IO18_30") (pintype "bidirectional"))
    )
    (net (code "62") (name "PWM3") (class "Default")
      (node (ref "IC5") (pin "8") (pinfunction "EN2_8") (pintype "input"))
      (node (ref "R41") (pin "1") (pinfunction "1_1") (pintype "passive"))
      (node (ref "U1") (pin "31") (pinfunction "IO19_31") (pintype "bidirectional"))
    )
    (net (code "63") (name "RI") (class "Default")
      (node (ref "IC3") (pin "2") (pinfunction "RI_2") (pintype "input"))
    )
    (net (code "64") (name "RTS") (class "Default")
      (node (ref "IC3") (pin "24") (pinfunction "RTS_24") (pintype "output"))
      (node (ref "R10") (pin "1") (pinfunction "1_1") (pintype "passive"))
      (node (ref "T1") (pin "E") (pinfunction "E_E") (pintype "passive"))
    )
    (net (code "65") (name "RXD") (class "Default")
      (node (ref "IC3") (pin "25") (pinfunction "RXD_25") (pintype "input"))
      (node (ref "R8") (pin "1") (pinfunction "1_1") (pintype "passive"))
    )
    (net (code "66") (name "RXD0") (class "Default")
      (node (ref "R7") (pin "2") (pinfunction "2_2") (pintype "passive"))
      (node (ref "U1") (pin "34") (pinfunction "RXD0_34") (pintype "bidirectional"))
    )
    (net (code "67") (name "TXD") (class "Default")
      (node (ref "IC3") (pin "26") (pinfunction "TXD_26") (pintype "output"))
      (node (ref "R7") (pin "1") (pinfunction "1_1") (pintype "passive"))
    )
    (net (code "68") (name "TXD0") (class "Default")
      (node (ref "R8") (pin "2") (pinfunction "2_2") (pintype "passive"))
      (node (ref "U1") (pin "35") (pinfunction "TXD0_35") (pintype "bidirectional"))
    )
    (net (code "69") (name "VBUS") (class "Default")
      (node (ref "CN1") (pin "VBUS") (pinfunction "VBUS_VBUS") (pintype "power_in"))
      (node (ref "D2") (pin "A") (pinfunction "A_A") (pintype "passive"))
      (node (ref "R1") (pin "1") (pinfunction "1_1") (pintype "passive"))
    )
    (net (code "70") (name "unconnected-(CN1-PadID)") (class "Default")
      (node (ref "CN1") (pin "ID") (pinfunction "ID_ID") (pintype "bidirectional"))
    )
    (net (code "71") (name "unconnected-(IC3-SUSPEND-Pad12)") (class "Default")
      (node (ref "IC3") (pin "12") (pinfunction "SUSPEND_12") (pintype "output"))
    )
    (net (code "72") (name "unconnected-(J1-Pad1)") (class "Default")
      (node (ref "J1") (pin "1") (pinfunction "1_1") (pintype "passive"))
    )
    (net (code "73") (name "unconnected-(J1-Pad4)") (class "Default")
      (node (ref "J1") (pin "4") (pinfunction "4_4") (pintype "passive"))
    )
    (net (code "74") (name "unconnected-(J1-Pad6)") (class "Default")
      (node (ref "J1") (pin "6") (pinfunction "6_6") (pintype "passive"))
    )
    (net (code "75") (name "unconnected-(U1-CLK-Pad20)") (class "Default")
      (node (ref "U1") (pin "20") (pinfunction "CLK_20") (pintype "bidirectional"))
    )
    (net (code "76") (name "unconnected-(U1-CMD-Pad19)") (class "Default")
      (node (ref "U1") (pin "19") (pinfunction "CMD_19") (pintype "bidirectional"))
    )
    (net (code "77") (name "unconnected-(U1-IO2-Pad24)") (class "Default")
      (node (ref "U1") (pin "24") (pinfunction "IO2_24") (pintype "bidirectional"))
    )
    (net (code "78") (name "unconnected-(U1-IO4-Pad26)") (class "Default")
      (node (ref "U1") (pin "26") (pinfunction "IO4_26") (pintype "bidirectional"))
    )
    (net (code "79") (name "unconnected-(U1-IO21-Pad33)") (class "Default")
      (node (ref "U1") (pin "33") (pinfunction "IO21_33") (pintype "bidirectional"))
    )
    (net (code "80") (name "unconnected-(U1-IO35-Pad7)") (class "Default")
      (node (ref "U1") (pin "7") (pinfunction "IO35_7") (pintype "input"))
    )
    (net (code "81") (name "unconnected-(U1-NC-Pad32)") (class "Default")
      (node (ref "U1") (pin "32") (pinfunction "NC_32") (pintype "bidirectional"))
    )
    (net (code "82") (name "unconnected-(U1-PadGND)") (class "Default")
      (node (ref "U1") (pin "GND") (pinfunction "GND_GND") (pintype "bidirectional"))
    )
    (net (code "83") (name "unconnected-(U1-SD1-Pad22)") (class "Default")
      (node (ref "U1") (pin "22") (pinfunction "SD1_22") (pintype "bidirectional"))
    )
    (net (code "84") (name "unconnected-(U1-SD2-Pad17)") (class "Default")
      (node (ref "U1") (pin "17") (pinfunction "SD2_17") (pintype "bidirectional"))
    )
    (net (code "85") (name "unconnected-(U1-SD3-Pad18)") (class "Default")
      (node (ref "U1") (pin "18") (pinfunction "SD3_18") (pintype "bidirectional"))
    )
    (net (code "86") (name "unconnected-(U1-SDO-Pad21)") (class "Default")
      (node (ref "U1") (pin "21") (pinfunction "SDO_21") (pintype "bidirectional"))
    )
    (net (code "87") (name "unconnected-(U1-SENSOR_VN-Pad5)") (class "Default")
      (node (ref "U1") (pin "5") (pinfunction "SENSOR_VN_5") (pintype "input"))
    )
    (net (code "88") (name "unconnected-(U1-SENSOR_VP-Pad4)") (class "Default")
      (node (ref "U1") (pin "4") (pinfunction "SENSOR_VP_4") (pintype "input"))
    )
    (net (code "89") (name "unconnected-(U2-ALERT-Pad3)") (class "Default")
      (node (ref "U2") (pin "3") (pinfunction "ALERT_3") (pintype "output"))
    )
    (net (code "90") (name "unconnected-(U3-INT-Pad5)") (class "Default")
      (node (ref "U3") (pin "5") (pinfunction "INT_5") (pintype "output"))
    )
  )
)
